# event_loading.net
KiCad netlist of a schematic drawn in Altium Designer
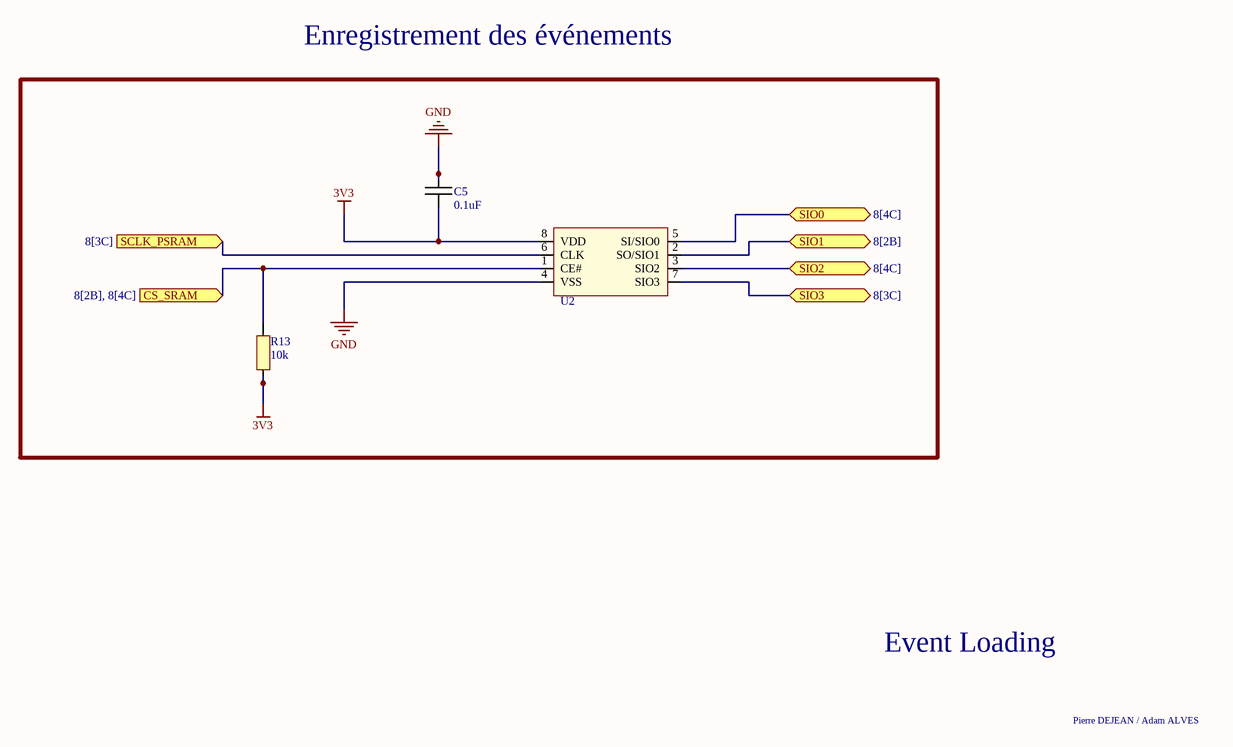
[diagram p0: event_loading.SchDoc]

(export (version "E")
  (design (tool "Eeschema 10.0.6"))
  (components
    (comp (ref "C5")
      (value "0.1uF")
      (footprint "CAPC1005X06N")
      (libsource (lib "SCHLibrary") (part "Capacitor"))
    )
    (comp (ref "R13")
      (value "10k")
      (footprint "RESC1005X06N")
      (libsource (lib "SCHLibrary") (part "Resistor"))
    )
    (comp (ref "U2")
      (value "IS66WVS1M8BLL-104NLI")
      (footprint "SOIC127P600X175-8N")
      (description "SRAM 8Mb, SerialRAM, 2.7V-3.6V, 104MHz, 8 pin SOIC 150 mil, RoHS")
      (libsource (lib "SCHLibrary") (part "SRAM"))
    )
  )
  (nets
    (net (code "1") (name "/CS_SRAM") (class "Default")
      (node (ref "R13") (pin "2") (pinfunction "2_2") (pintype "passive"))
      (node (ref "U2") (pin "1") (pinfunction "CE#_1") (pintype "passive"))
    )
    (net (code "2") (name "/SCLK_PSRAM") (class "Default")
      (node (ref "U2") (pin "6") (pinfunction "CLK_6") (pintype "passive"))
    )
    (net (code "3") (name "/SIO0") (class "Default")
      (node (ref "U2") (pin "5") (pinfunction "SI/SIO0_5") (pintype "passive"))
    )
    (net (code "4") (name "/SIO1") (class "Default")
      (node (ref "U2") (pin "2") (pinfunction "SO/SIO1_2") (pintype "passive"))
    )
    (net (code "5") (name "/SIO2") (class "Default")
      (node (ref "U2") (pin "3") (pinfunction "SIO2_3") (pintype "passive"))
    )
    (net (code "6") (name "/SIO3") (class "Default")
      (node (ref "U2") (pin "7") (pinfunction "SIO3_7") (pintype "passive"))
    )
    (net (code "7") (name "3V3") (class "Default")
      (node (ref "C5") (pin "2") (pinfunction "2_2") (pintype "passive"))
      (node (ref "R13") (pin "1") (pinfunction "1_1") (pintype "passive"))
      (node (ref "U2") (pin "8") (pinfunction "VDD_8") (pintype "passive"))
    )
    (net (code "8") (name "GND") (class "Default")
      (node (ref "C5") (pin "1") (pinfunction "1_1") (pintype "passive"))
      (node (ref "U2") (pin "4") (pinfunction "VSS_4") (pintype "passive"))
    )
  )
)
